# Active_Electrode.net
KiCad netlist of a schematic drawn in EAGLE
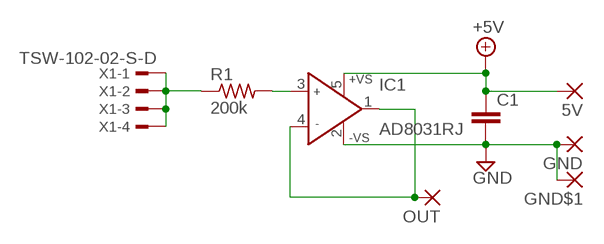
[diagram p0: schematic, sheet 1]

(export (version "E")
  (design (tool "Eeschema 10.0.6"))
  (components
    (comp (ref "5V")
      (value "1,6/0,9")
      (footprint "eagle-import:1,6_0,9")
      (libsource (lib "eagle-import") (part "1,6/0,9"))
    )
    (comp (ref "C1")
      (value "C-EUC1206")
      (footprint "eagle-import:C1206")
      (libsource (lib "eagle-import") (part "C-EUC1206"))
    )
    (comp (ref "GND")
      (value "1,6/0,9")
      (footprint "eagle-import:1,6_0,9")
      (libsource (lib "eagle-import") (part "1,6/0,9"))
    )
    (comp (ref "GND$1")
      (value "1,6/0,9")
      (footprint "eagle-import:1,6_0,9")
      (libsource (lib "eagle-import") (part "1,6/0,9"))
    )
    (comp (ref "IC1")
      (value "AD8031RJ")
      (footprint "eagle-import:SOT23-5")
      (fields (field (name "MPN") "AD8031ARTZ-REEL7"))
      (libsource (lib "eagle-import") (part "AD8031RJ"))
    )
    (comp (ref "OUT")
      (value "1,6/0,9")
      (footprint "eagle-import:1,6_0,9")
      (libsource (lib "eagle-import") (part "1,6/0,9"))
    )
    (comp (ref "R1")
      (value "200k")
      (footprint "eagle-import:M1206")
      (libsource (lib "eagle-import") (part "R-US_M1206"))
    )
    (comp (ref "X1")
      (value "TSW-102-02-S-D")
      (footprint "eagle-import:TSW-102-02-S-D")
      (libsource (lib "eagle-import") (part "TSW-102-02-S-D"))
    )
  )
  (nets
    (net (code "1") (name "+5V") (class "Default")
      (node (ref "5V") (pin "1") (pinfunction "P_1") (pintype "passive"))
      (node (ref "C1") (pin "1") (pinfunction "1_1") (pintype "passive"))
      (node (ref "IC1") (pin "5") (pinfunction "+VS_5") (pintype "input"))
    )
    (net (code "2") (name "GND") (class "Default")
      (node (ref "C1") (pin "2") (pinfunction "2_2") (pintype "passive"))
      (node (ref "GND") (pin "1") (pinfunction "P_1") (pintype "passive"))
      (node (ref "GND$1") (pin "1") (pinfunction "P_1") (pintype "passive"))
      (node (ref "IC1") (pin "2") (pinfunction "-VS_2") (pintype "input"))
    )
    (net (code "3") (name "Net-(IC1-IN+)") (class "Default")
      (node (ref "IC1") (pin "3") (pinfunction "IN+_3") (pintype "input"))
      (node (ref "R1") (pin "2") (pinfunction "2_2") (pintype "passive"))
    )
    (net (code "4") (name "Net-(IC1-IN-)") (class "Default")
      (node (ref "IC1") (pin "1") (pinfunction "OUT_1") (pintype "output"))
      (node (ref "IC1") (pin "4") (pinfunction "IN-_4") (pintype "input"))
      (node (ref "OUT") (pin "1") (pinfunction "P_1") (pintype "passive"))
    )
    (net (code "5") (name "Net-(X1B-1)") (class "Default")
      (node (ref "R1") (pin "1") (pinfunction "1_1") (pintype "passive"))
      (node (ref "X1") (pin "1") (pinfunction "1_1") (pintype "passive"))
      (node (ref "X1") (pin "2") (pinfunction "1_2") (pintype "passive"))
      (node (ref "X1") (pin "3") (pinfunction "1_3") (pintype "passive"))
      (node (ref "X1") (pin "4") (pinfunction "1_4") (pintype "passive"))
    )
  )
)
